# LB_BIT_p3_USBPOWER-v03_rev1.net
KiCad netlist of a schematic drawn in EAGLE
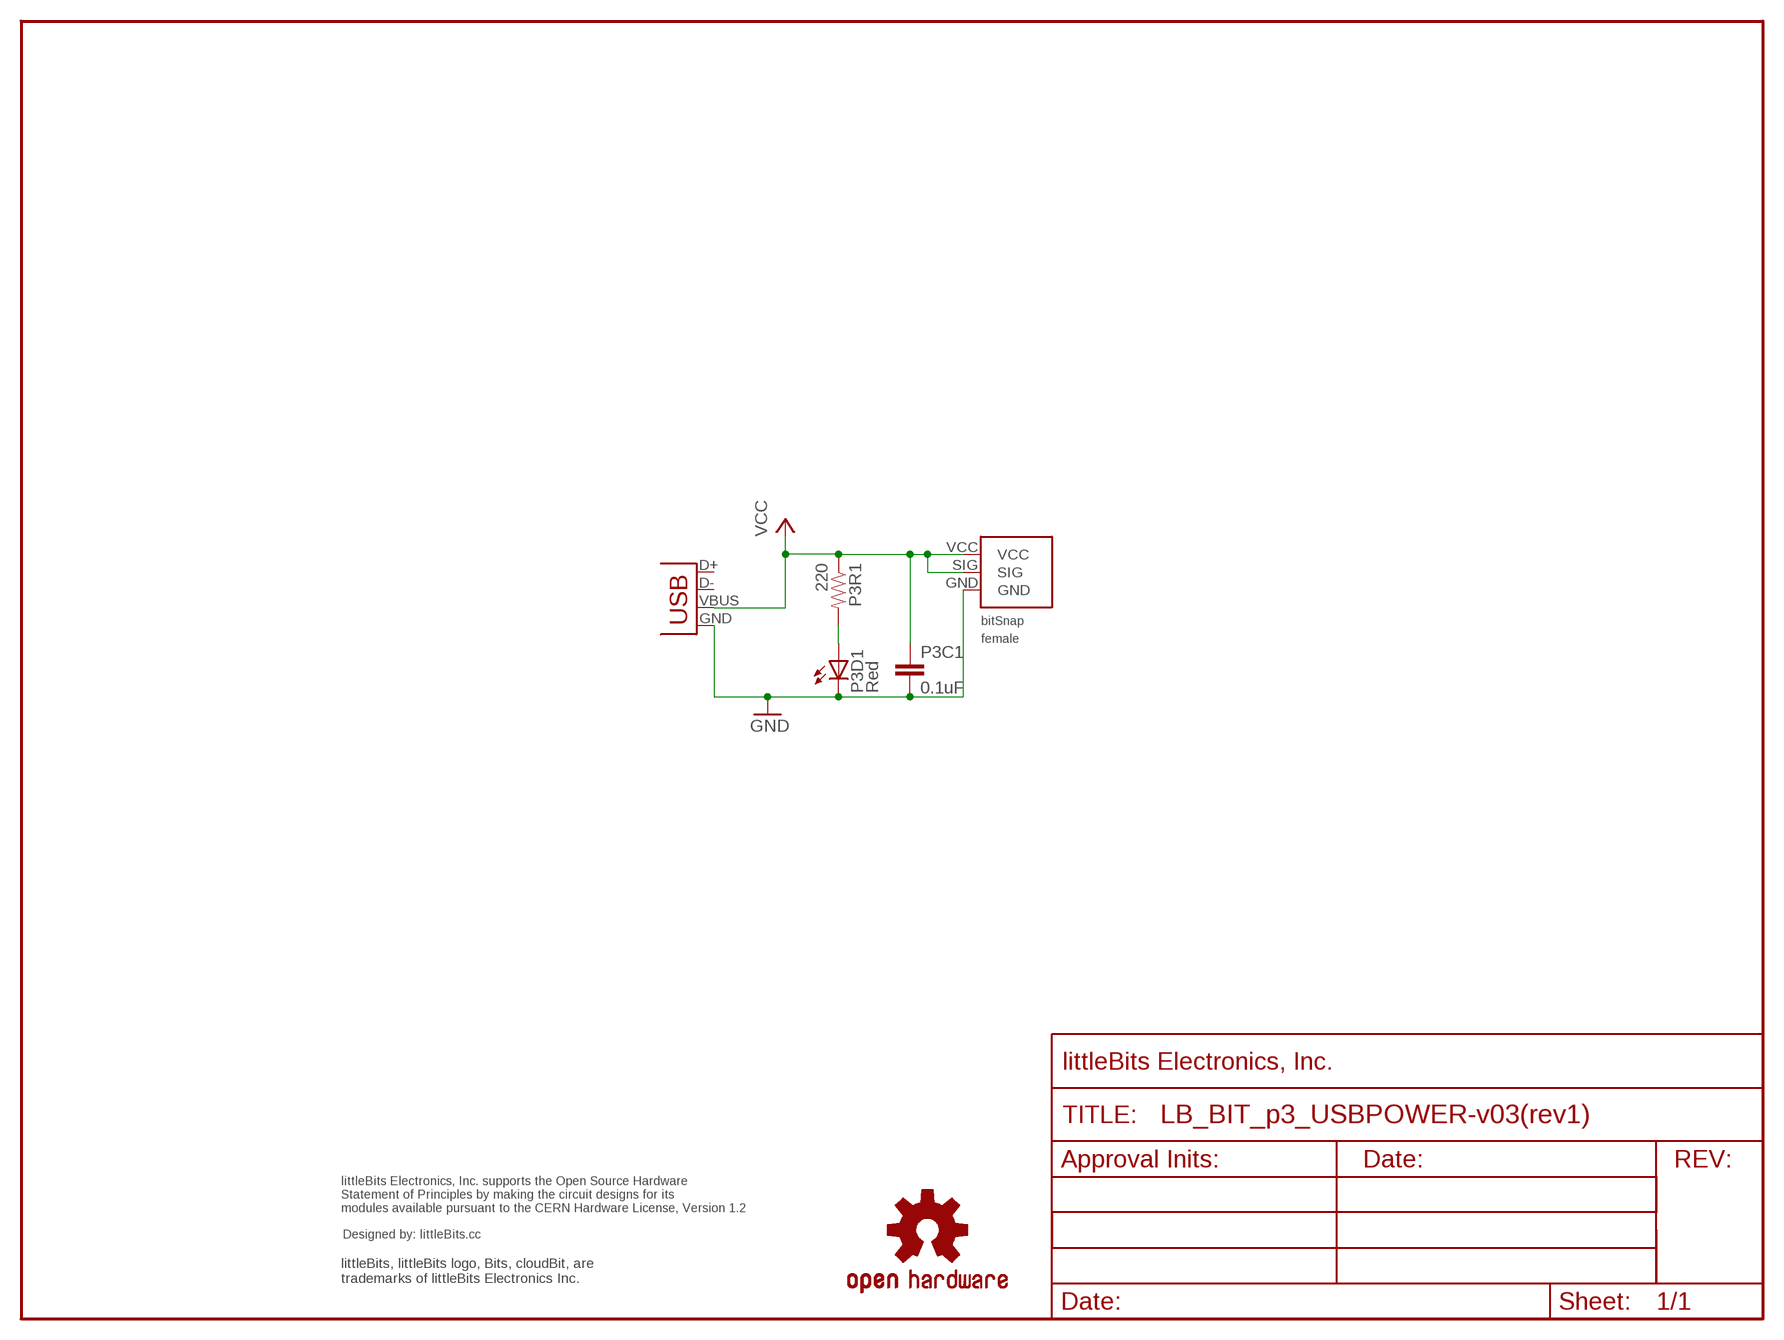
[diagram p0: schematic, sheet 1]

(export (version "E")
  (design (tool "Eeschema 10.0.6"))
  (components
    (comp (ref "P3BSF1")
      (value "BITSNAP_V03_FEMALE")
      (footprint "eagle-import:BITSNAP_V03_FEMALE")
      (libsource (lib "eagle-import") (part "BITSNAP_V03_FEMALE"))
    )
    (comp (ref "P3C1")
      (value "0.1uF")
      (footprint "eagle-import:0603-CAP")
      (libsource (lib "eagle-import") (part "CAP0603-CAP"))
    )
    (comp (ref "P3D1")
      (value "Red")
      (footprint "eagle-import:LED-1206")
      (libsource (lib "eagle-import") (part "LED1206"))
    )
    (comp (ref "P3R1")
      (value "220")
      (footprint "eagle-import:0603-RES")
      (libsource (lib "eagle-import") (part "RESISTOR0603-RES"))
    )
    (comp (ref "P3X1")
      (value "USB-MICROB-AUK_TH")
      (footprint "eagle-import:USB-MICROB-AUK")
      (libsource (lib "eagle-import") (part "USB-MICROB-AUK_TH"))
    )
    (comp (ref "U$1")
      (value "OSHWCREDIT")
      (footprint "eagle-import:OSHWCREDIT")
      (libsource (lib "eagle-import") (part "OSHWCREDIT"))
    )
    (comp (ref "U$2")
      (value "FRAME-LETTER-OHWOHW")
      (footprint "eagle-import:FABDWG01-OHW")
      (libsource (lib "eagle-import") (part "FRAME-LETTER-OHWOHW"))
    )
    (comp (ref "U$3")
      (value "OSHW-LOGOL")
      (footprint "eagle-import:OSHW-LOGO-L")
      (libsource (lib "eagle-import") (part "OSHW-LOGOL"))
    )
  )
  (nets
    (net (code "1") (name "GND") (class "Default")
      (node (ref "P3BSF1") (pin "GND") (pinfunction "GND_GND") (pintype "bidirectional"))
      (node (ref "P3C1") (pin "2") (pinfunction "2_2") (pintype "passive"))
      (node (ref "P3D1") (pin "C") (pinfunction "C_C") (pintype "passive"))
      (node (ref "P3X1") (pin "GND") (pinfunction "GND_GND") (pintype "bidirectional"))
    )
    (net (code "2") (name "Net-(P3D1-PadA)") (class "Default")
      (node (ref "P3D1") (pin "A") (pinfunction "A_A") (pintype "passive"))
      (node (ref "P3R1") (pin "2") (pinfunction "2_2") (pintype "passive"))
    )
    (net (code "3") (name "VCC") (class "Default")
      (node (ref "P3BSF1") (pin "SIG") (pinfunction "SIG_SIG") (pintype "bidirectional"))
      (node (ref "P3BSF1") (pin "VCC") (pinfunction "VCC_VCC") (pintype "bidirectional"))
      (node (ref "P3C1") (pin "1") (pinfunction "1_1") (pintype "passive"))
      (node (ref "P3R1") (pin "1") (pinfunction "1_1") (pintype "passive"))
      (node (ref "P3X1") (pin "VBUS") (pinfunction "VBUS_VBUS") (pintype "bidirectional"))
    )
    (net (code "4") (name "unconnected-(P3X1-PadD+)") (class "Default")
      (node (ref "P3X1") (pin "D+") (pinfunction "D+_D+") (pintype "bidirectional"))
    )
    (net (code "5") (name "unconnected-(P3X1-PadD-)") (class "Default")
      (node (ref "P3X1") (pin "D-") (pinfunction "D-_D-") (pintype "bidirectional"))
    )
  )
)
